# mcu.net
KiCad netlist of a schematic drawn in Altium Designer
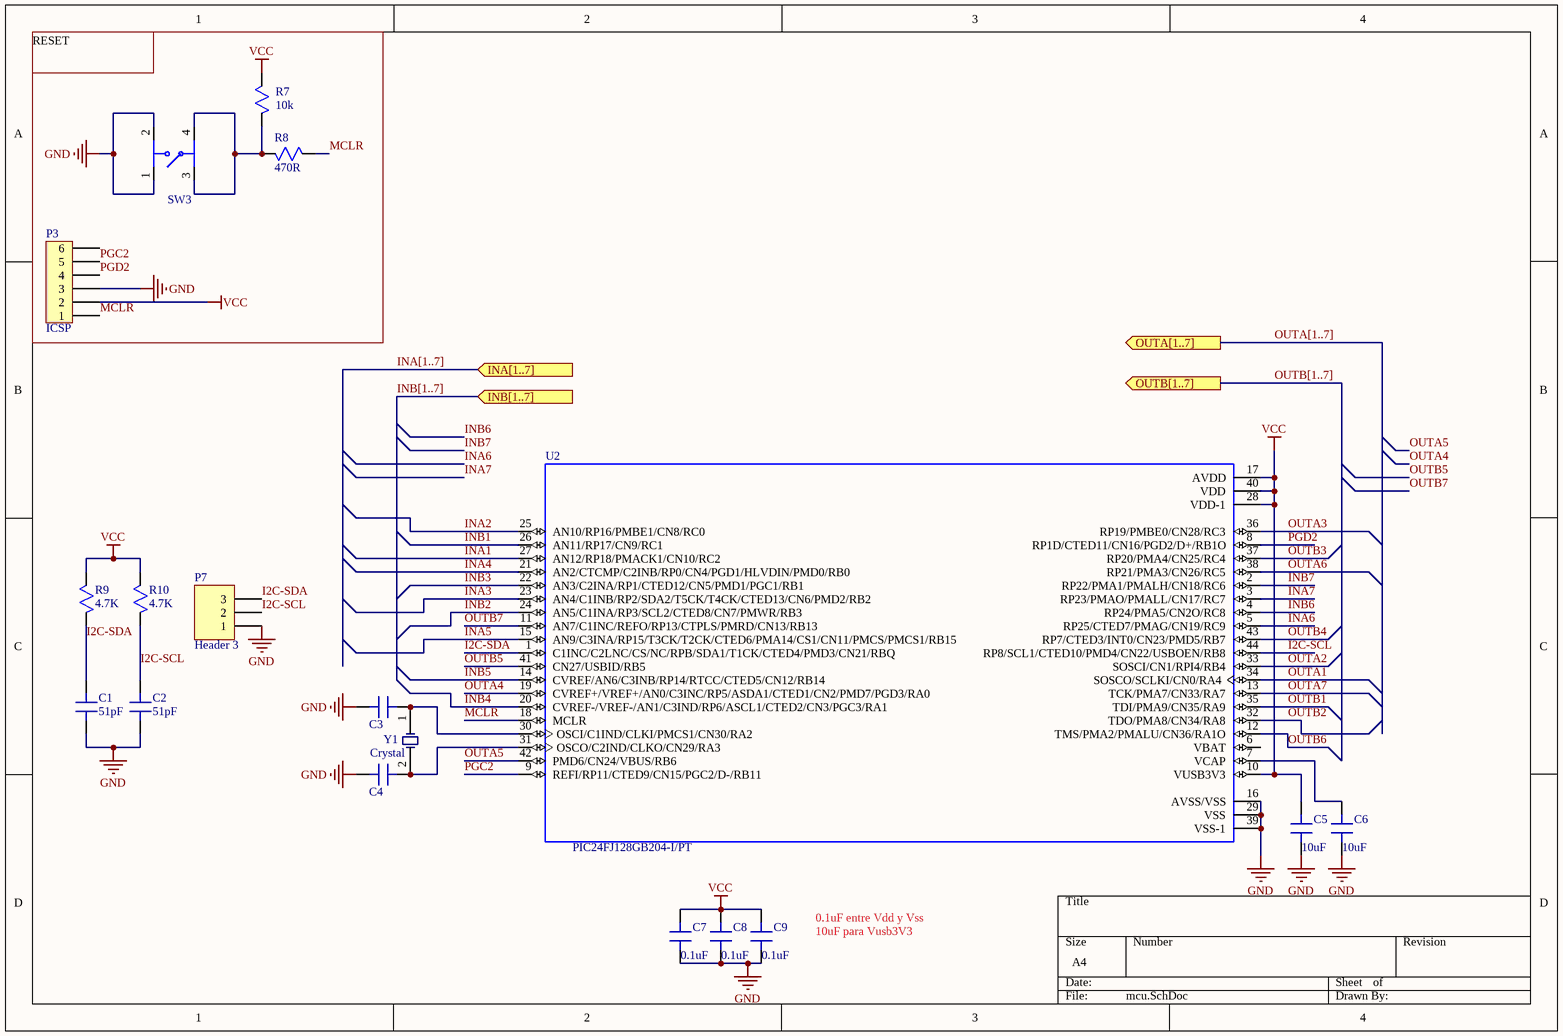
[diagram p0: mcu.SchDoc]

(export (version "E")
  (design (tool "Eeschema 10.0.6"))
  (components
    (comp (ref "C1")
      (value "51pF")
      (footprint "Capacitor0805")
      (description "Ceramic Capacitor")
      (fields
        (field (name "DIGI-KEY PART NUMBER") "311-4223-1-ND")
        (field (name "MANUFACTURERS PART NUMBER") "CC0805JRNPO0BN510")
      )
      (libsource (lib "PAT_Library") (part "CapacitorSMD"))
    )
    (comp (ref "C2")
      (value "51pF")
      (footprint "Capacitor0805")
      (description "Ceramic Capacitor")
      (fields
        (field (name "DIGI-KEY PART NUMBER") "311-4223-1-ND")
        (field (name "MANUFACTURERS PART NUMBER") "CC0805JRNPO0BN510")
      )
      (libsource (lib "PAT_Library") (part "CapacitorSMD"))
    )
    (comp (ref "C3")
      (value "6pF")
      (footprint "Capacitor0805")
      (description "Ceramic Capacitor")
      (fields
        (field (name "DIGI-KEY PART NUMBER") "311-4149-1-ND")
        (field (name "MANUFACTURERS PART NUMBER") "CC0805CRNPO9BN6R0")
      )
      (libsource (lib "PAT_Library") (part "CapacitorSMD"))
    )
    (comp (ref "C4")
      (value "6pF")
      (footprint "Capacitor0805")
      (description "Ceramic Capacitor")
      (fields
        (field (name "DIGI-KEY PART NUMBER") "311-4149-1-ND")
        (field (name "MANUFACTURERS PART NUMBER") "CC0805CRNPO9BN6R0")
      )
      (libsource (lib "PAT_Library") (part "CapacitorSMD"))
    )
    (comp (ref "C5")
      (value "10uF")
      (footprint "Capacitor0805")
      (description "Ceramic Capacitor")
      (fields
        (field (name "DIGI-KEY PART NUMBER") "311-1355-1-ND")
        (field (name "MANUFACTURERS PART NUMBER") "CC0805ZKY5V6BB106")
      )
      (libsource (lib "ComponentesTruffaV2") (part "CapacitorSMD"))
    )
    (comp (ref "C6")
      (value "10uF")
      (footprint "Capacitor0805")
      (description "Ceramic Capacitor")
      (fields
        (field (name "DIGI-KEY PART NUMBER") "311-1355-1-ND")
        (field (name "MANUFACTURERS PART NUMBER") "CC0805ZKY5V6BB106")
      )
      (libsource (lib "ComponentesTruffaV2") (part "CapacitorSMD"))
    )
    (comp (ref "C7")
      (value "0.1uF")
      (footprint "Capacitor0805")
      (description "Ceramic Capacitor")
      (fields
        (field (name "DIGI-KEY PART NUMBER") "311-1141-1-ND")
        (field (name "MANUFACTURERS PART NUMBER") "CC0805KRX7R8BB104")
      )
      (libsource (lib "ComponentesTruffaV2") (part "CapacitorSMD"))
    )
    (comp (ref "C8")
      (value "0.1uF")
      (footprint "Capacitor0805")
      (description "Ceramic Capacitor")
      (fields
        (field (name "DIGI-KEY PART NUMBER") "311-1141-1-ND")
        (field (name "MANUFACTURERS PART NUMBER") "CC0805KRX7R8BB104")
      )
      (libsource (lib "ComponentesTruffaV2") (part "CapacitorSMD"))
    )
    (comp (ref "C9")
      (value "0.1uF")
      (footprint "Capacitor0805")
      (description "Ceramic Capacitor")
      (fields
        (field (name "DIGI-KEY PART NUMBER") "311-1141-1-ND")
        (field (name "MANUFACTURERS PART NUMBER") "CC0805KRX7R8BB104")
      )
      (libsource (lib "ComponentesTruffaV2") (part "CapacitorSMD"))
    )
    (comp (ref "P3")
      (value "ICSP")
      (footprint "MALE6PIN")
      (description "Pin Header Male 6 Pins Pitch 2.54mm")
      (fields
        (field (name "DIGI-KEY PART NUMBER") "952-2269-ND")
        (field (name "MANUFACTURERS PART NUMBER") "M20-9990645")
      )
      (libsource (lib "PAT Connectors Board") (part "PHM1x6P2.54"))
    )
    (comp (ref "P7")
      (value "Header 3")
      (footprint "HDR1X3")
      (description "Header, 3-Pin")
      (libsource (lib "Miscellaneous Connectors") (part "Header 3"))
    )
    (comp (ref "R7")
      (value "10k")
      (footprint "ResistorSMD0805")
      (description "Chip Resistor SMD")
      (fields
        (field (name "DIGI-KEY PART NUMBER") "311-10KARCT-ND")
        (field (name "MANUFACTURERS PART NUMBER") "RC0805JR-0710KL")
      )
      (libsource (lib "PAT_Library") (part "ResistorSMD"))
    )
    (comp (ref "R8")
      (value "470R")
      (footprint "ResistorSMD0805")
      (description "Chip Resistor SMD")
      (fields
        (field (name "DIGI-KEY PART NUMBER") "311-470CRCT-ND")
        (field (name "MANUFACTURERS PART NUMBER") "RC0805FR-07470RL")
      )
      (libsource (lib "PAT_Library") (part "ResistorSMD"))
    )
    (comp (ref "R9")
      (value "4.7K")
      (footprint "ResistorSMD0805")
      (description "Chip Resistor SMD")
      (fields
        (field (name "DIGI-KEY PART NUMBER") "311-4.70KCRCT-ND")
        (field (name "MANUFACTURERS PART NUMBER") "RC0805FR-074K7L")
      )
      (libsource (lib "PAT_Library") (part "ResistorSMD"))
    )
    (comp (ref "R10")
      (value "4.7K")
      (footprint "ResistorSMD0805")
      (description "Chip Resistor SMD")
      (fields
        (field (name "DIGI-KEY PART NUMBER") "311-4.70KCRCT-ND")
        (field (name "MANUFACTURERS PART NUMBER") "RC0805FR-074K7L")
      )
      (libsource (lib "PAT_Library") (part "ResistorSMD"))
    )
    (comp (ref "SW3")
      (value "Tactile Switch")
      (footprint "TactileSwitch")
      (description "Switch Contact")
      (fields
        (field (name "DIGI-KEY PART NUMBER") "CKN9112CT-ND")
        (field (name "MANUFACTURERS PART NUMBER") "PTS645SM43SMTR92 LFS")
      )
      (libsource (lib "PAT_Library") (part "Tactile Switch"))
    )
    (comp (ref "U2")
      (value "PIC24FJ128GB204-I/PT")
      (footprint "QFP80P1200X1200X120-44N")
      (description "128KB Flash, 8KB RAM, 16 MIPS, USB OTG, Crypto, 44 TQFP 10x10x1mm TRAY")
      (fields (field (name "DIGI-KEY PART NUMBER") "PIC24FJ128GB204-I/PT-ND"))
      (libsource (lib "PIC24FJ128GB204-I_PT") (part "PIC24FJ128GB204-I/PT"))
    )
    (comp (ref "Y1")
      (value "Crystal")
      (footprint "CRYSTALSMDMini")
      (description "Crystal SMD")
      (fields
        (field (name "DIGI-KEY PART NUMBER") "XC1842CT-ND")
        (field (name "MANUFACTURERS PART NUMBER") "ECS-240-8-30B-CKM")
      )
      (libsource (lib "PAT_Library") (part "Crystal"))
    )
  )
  (nets
    (net (code "1") (name "/I2C-SCL") (class "Default")
      (node (ref "C2") (pin "1") (pinfunction "1_1") (pintype "passive"))
      (node (ref "P7") (pin "2") (pinfunction "2_2") (pintype "passive"))
      (node (ref "R10") (pin "1") (pinfunction "1_1") (pintype "passive"))
      (node (ref "U2") (pin "44") (pinfunction "RP8/SCL1/CTED10/PMD4/CN22/USBOEN/RB8_44") (pintype "bidirectional"))
    )
    (net (code "2") (name "/I2C-SDA") (class "Default")
      (node (ref "C1") (pin "1") (pinfunction "1_1") (pintype "passive"))
      (node (ref "P7") (pin "3") (pinfunction "3_3") (pintype "passive"))
      (node (ref "R9") (pin "1") (pinfunction "1_1") (pintype "passive"))
      (node (ref "U2") (pin "1") (pinfunction "C1INC/C2LNC/CS/NC/RPB/SDA1/T1CK/CTED4/PMD3/CN21/RBQ_1") (pintype "bidirectional"))
    )
    (net (code "3") (name "/INA1") (class "Default")
      (node (ref "U2") (pin "27") (pinfunction "AN12/RP18/PMACK1/CN10/RC2_27") (pintype "bidirectional"))
    )
    (net (code "4") (name "/INA2") (class "Default")
      (node (ref "U2") (pin "25") (pinfunction "AN10/RP16/PMBE1/CN8/RC0_25") (pintype "bidirectional"))
    )
    (net (code "5") (name "/INA3") (class "Default")
      (node (ref "U2") (pin "23") (pinfunction "AN4/C1INB/RP2/SDA2/T5CK/T4CK/CTED13/CN6/PMD2/RB2_23") (pintype "bidirectional"))
    )
    (net (code "6") (name "/INA4") (class "Default")
      (node (ref "U2") (pin "21") (pinfunction "AN2/CTCMP/C2INB/RP0/CN4/PGD1/HLVDIN/PMD0/RB0_21") (pintype "bidirectional"))
    )
    (net (code "7") (name "/INA5") (class "Default")
      (node (ref "U2") (pin "15") (pinfunction "AN9/C3INA/RP15/T3CK/T2CK/CTED6/PMA14/CS1/CN11/PMCS/PMCS1/RB15_15") (pintype "bidirectional"))
    )
    (net (code "8") (name "/INA6") (class "Default")
      (node (ref "U2") (pin "5") (pinfunction "RP25/CTED7/PMAG/CN19/RC9_5") (pintype "bidirectional"))
    )
    (net (code "9") (name "/INA7") (class "Default")
      (node (ref "U2") (pin "3") (pinfunction "RP23/PMAO/PMALL/CN17/RC7_3") (pintype "bidirectional"))
    )
    (net (code "11") (name "/INB1") (class "Default")
      (node (ref "U2") (pin "26") (pinfunction "AN11/RP17/CN9/RC1_26") (pintype "bidirectional"))
    )
    (net (code "12") (name "/INB2") (class "Default")
      (node (ref "U2") (pin "24") (pinfunction "AN5/C1INA/RP3/SCL2/CTED8/CN7/PMWR/RB3_24") (pintype "bidirectional"))
    )
    (net (code "13") (name "/INB3") (class "Default")
      (node (ref "U2") (pin "22") (pinfunction "AN3/C2INA/RP1/CTED12/CN5/PMD1/PGC1/RB1_22") (pintype "bidirectional"))
    )
    (net (code "14") (name "/INB4") (class "Default")
      (node (ref "U2") (pin "20") (pinfunction "CVREF-/VREF-/AN1/C3IND/RP6/ASCL1/CTED2/CN3/PGC3/RA1_20") (pintype "bidirectional"))
    )
    (net (code "15") (name "/INB5") (class "Default")
      (node (ref "U2") (pin "14") (pinfunction "CVREF/AN6/C3INB/RP14/RTCC/CTED5/CN12/RB14_14") (pintype "bidirectional"))
    )
    (net (code "16") (name "/INB6") (class "Default")
      (node (ref "U2") (pin "4") (pinfunction "RP24/PMA5/CN2O/RC8_4") (pintype "bidirectional"))
    )
    (net (code "17") (name "/INB7") (class "Default")
      (node (ref "U2") (pin "2") (pinfunction "RP22/PMA1/PMALH/CN18/RC6_2") (pintype "bidirectional"))
    )
    (net (code "19") (name "/MCLR") (class "Default")
      (node (ref "P3") (pin "1") (pinfunction "1_1") (pintype "passive"))
      (node (ref "R8") (pin "2") (pinfunction "2_2") (pintype "passive"))
      (node (ref "U2") (pin "18") (pinfunction "MCLR_18") (pintype "bidirectional"))
    )
    (net (code "20") (name "/OUTA1") (class "Default")
      (node (ref "U2") (pin "34") (pinfunction "SOSCO/SCLKI/CN0/RA4_34") (pintype "bidirectional"))
    )
    (net (code "21") (name "/OUTA2") (class "Default")
      (node (ref "U2") (pin "33") (pinfunction "SOSCI/CN1/RPI4/RB4_33") (pintype "bidirectional"))
    )
    (net (code "22") (name "/OUTA3") (class "Default")
      (node (ref "U2") (pin "36") (pinfunction "RP19/PMBE0/CN28/RC3_36") (pintype "bidirectional"))
    )
    (net (code "23") (name "/OUTA4") (class "Default")
      (node (ref "U2") (pin "19") (pinfunction "CVREF+/VREF+/AN0/C3INC/RP5/ASDA1/CTED1/CN2/PMD7/PGD3/RA0_19") (pintype "bidirectional"))
    )
    (net (code "24") (name "/OUTA5") (class "Default")
      (node (ref "U2") (pin "42") (pinfunction "PMD6/CN24/VBUS/RB6_42") (pintype "bidirectional"))
    )
    (net (code "25") (name "/OUTA6") (class "Default")
      (node (ref "U2") (pin "38") (pinfunction "RP21/PMA3/CN26/RC5_38") (pintype "bidirectional"))
    )
    (net (code "26") (name "/OUTA7") (class "Default")
      (node (ref "U2") (pin "13") (pinfunction "TCK/PMA7/CN33/RA7_13") (pintype "bidirectional"))
    )
    (net (code "28") (name "/OUTB1") (class "Default")
      (node (ref "U2") (pin "35") (pinfunction "TDI/PMA9/CN35/RA9_35") (pintype "bidirectional"))
    )
    (net (code "29") (name "/OUTB2") (class "Default")
      (node (ref "U2") (pin "32") (pinfunction "TDO/PMA8/CN34/RA8_32") (pintype "bidirectional"))
    )
    (net (code "30") (name "/OUTB3") (class "Default")
      (node (ref "U2") (pin "37") (pinfunction "RP20/PMA4/CN25/RC4_37") (pintype "bidirectional"))
    )
    (net (code "31") (name "/OUTB4") (class "Default")
      (node (ref "U2") (pin "43") (pinfunction "RP7/CTED3/INT0/CN23/PMD5/RB7_43") (pintype "bidirectional"))
    )
    (net (code "32") (name "/OUTB5") (class "Default")
      (node (ref "U2") (pin "41") (pinfunction "CN27/USBID/RB5_41") (pintype "bidirectional"))
    )
    (net (code "33") (name "/OUTB6") (class "Default")
      (node (ref "U2") (pin "12") (pinfunction "TMS/PMA2/PMALU/CN36/RA1O_12") (pintype "bidirectional"))
    )
    (net (code "34") (name "/OUTB7") (class "Default")
      (node (ref "U2") (pin "11") (pinfunction "AN7/C1INC/REFO/RP13/CTPLS/PMRD/CN13/RB13_11") (pintype "bidirectional"))
    )
    (net (code "36") (name "/PGC2") (class "Default")
      (node (ref "P3") (pin "5") (pinfunction "5_5") (pintype "passive"))
      (node (ref "U2") (pin "9") (pinfunction "REFI/RP11/CTED9/CN15/PGC2/D-/RB11_9") (pintype "bidirectional"))
    )
    (net (code "37") (name "/PGD2") (class "Default")
      (node (ref "P3") (pin "4") (pinfunction "4_4") (pintype "passive"))
      (node (ref "U2") (pin "8") (pinfunction "RP1D/CTED11/CN16/PGD2/D+/RB1O_8") (pintype "bidirectional"))
    )
    (net (code "38") (name "GND") (class "Default")
      (node (ref "C1") (pin "2") (pinfunction "2_2") (pintype "passive"))
      (node (ref "C2") (pin "2") (pinfunction "2_2") (pintype "passive"))
      (node (ref "C3") (pin "1") (pinfunction "1_1") (pintype "passive"))
      (node (ref "C4") (pin "1") (pinfunction "1_1") (pintype "passive"))
      (node (ref "C5") (pin "1") (pinfunction "1_1") (pintype "passive"))
      (node (ref "C6") (pin "1") (pinfunction "1_1") (pintype "passive"))
      (node (ref "C7") (pin "1") (pinfunction "1_1") (pintype "passive"))
      (node (ref "C8") (pin "1") (pinfunction "1_1") (pintype "passive"))
      (node (ref "C9") (pin "1") (pinfunction "1_1") (pintype "passive"))
      (node (ref "P3") (pin "3") (pinfunction "3_3") (pintype "passive"))
      (node (ref "P7") (pin "1") (pinfunction "1_1") (pintype "passive"))
      (node (ref "SW3") (pin "1") (pinfunction "1_1") (pintype "passive"))
      (node (ref "SW3") (pin "2") (pinfunction "2_2") (pintype "passive"))
      (node (ref "U2") (pin "16") (pinfunction "AVSS/VSS_16") (pintype "power_in"))
      (node (ref "U2") (pin "29") (pinfunction "VSS_29") (pintype "power_in"))
      (node (ref "U2") (pin "39") (pinfunction "VSS-1_39") (pintype "power_in"))
    )
    (net (code "39") (name "Net-(R7-Pad1)") (class "Default")
      (node (ref "R7") (pin "1") (pinfunction "1_1") (pintype "passive"))
      (node (ref "R8") (pin "1") (pinfunction "1_1") (pintype "passive"))
      (node (ref "SW3") (pin "3") (pinfunction "3_3") (pintype "passive"))
      (node (ref "SW3") (pin "4") (pinfunction "4_4") (pintype "passive"))
    )
    (net (code "40") (name "Net-(U2-OSCI{slash}C1IND{slash}CLKI{slash}PMCS1{slash}CN30{slash}RA2)") (class "Default")
      (node (ref "C3") (pin "2") (pinfunction "2_2") (pintype "passive"))
      (node (ref "U2") (pin "30") (pinfunction "OSCI/C1IND/CLKI/PMCS1/CN30/RA2_30") (pintype "bidirectional"))
      (node (ref "Y1") (pin "1") (pinfunction "1_1") (pintype "passive"))
    )
    (net (code "41") (name "Net-(U2-OSCO{slash}C2IND{slash}CLKO{slash}CN29{slash}RA3)") (class "Default")
      (node (ref "C4") (pin "2") (pinfunction "2_2") (pintype "passive"))
      (node (ref "U2") (pin "31") (pinfunction "OSCO/C2IND/CLKO/CN29/RA3_31") (pintype "bidirectional"))
      (node (ref "Y1") (pin "2") (pinfunction "2_2") (pintype "passive"))
    )
    (net (code "42") (name "Net-(U2-VCAP)") (class "Default")
      (node (ref "C6") (pin "2") (pinfunction "2_2") (pintype "passive"))
      (node (ref "U2") (pin "7") (pinfunction "VCAP_7") (pintype "bidirectional"))
    )
    (net (code "43") (name "VCC") (class "Default")
      (node (ref "C5") (pin "2") (pinfunction "2_2") (pintype "passive"))
      (node (ref "C7") (pin "2") (pinfunction "2_2") (pintype "passive"))
      (node (ref "C8") (pin "2") (pinfunction "2_2") (pintype "passive"))
      (node (ref "C9") (pin "2") (pinfunction "2_2") (pintype "passive"))
      (node (ref "P3") (pin "2") (pinfunction "2_2") (pintype "passive"))
      (node (ref "R10") (pin "2") (pinfunction "2_2") (pintype "passive"))
      (node (ref "R7") (pin "2") (pinfunction "2_2") (pintype "passive"))
      (node (ref "R9") (pin "2") (pinfunction "2_2") (pintype "passive"))
      (node (ref "U2") (pin "10") (pinfunction "VUSB3V3_10") (pintype "bidirectional"))
      (node (ref "U2") (pin "17") (pinfunction "AVDD_17") (pintype "power_in"))
      (node (ref "U2") (pin "28") (pinfunction "VDD-1_28") (pintype "power_in"))
      (node (ref "U2") (pin "40") (pinfunction "VDD_40") (pintype "power_in"))
    )
    (net (code "44") (name "unconnected-(P3-Pad6)") (class "Default")
      (node (ref "P3") (pin "6") (pinfunction "6_6") (pintype "passive"))
    )
    (net (code "45") (name "unconnected-(U2-VBAT-Pad6)") (class "Default")
      (node (ref "U2") (pin "6") (pinfunction "VBAT_6") (pintype "bidirectional"))
    )
  )
)
